# tx_path.net
KiCad netlist of a schematic drawn in Altium Designer
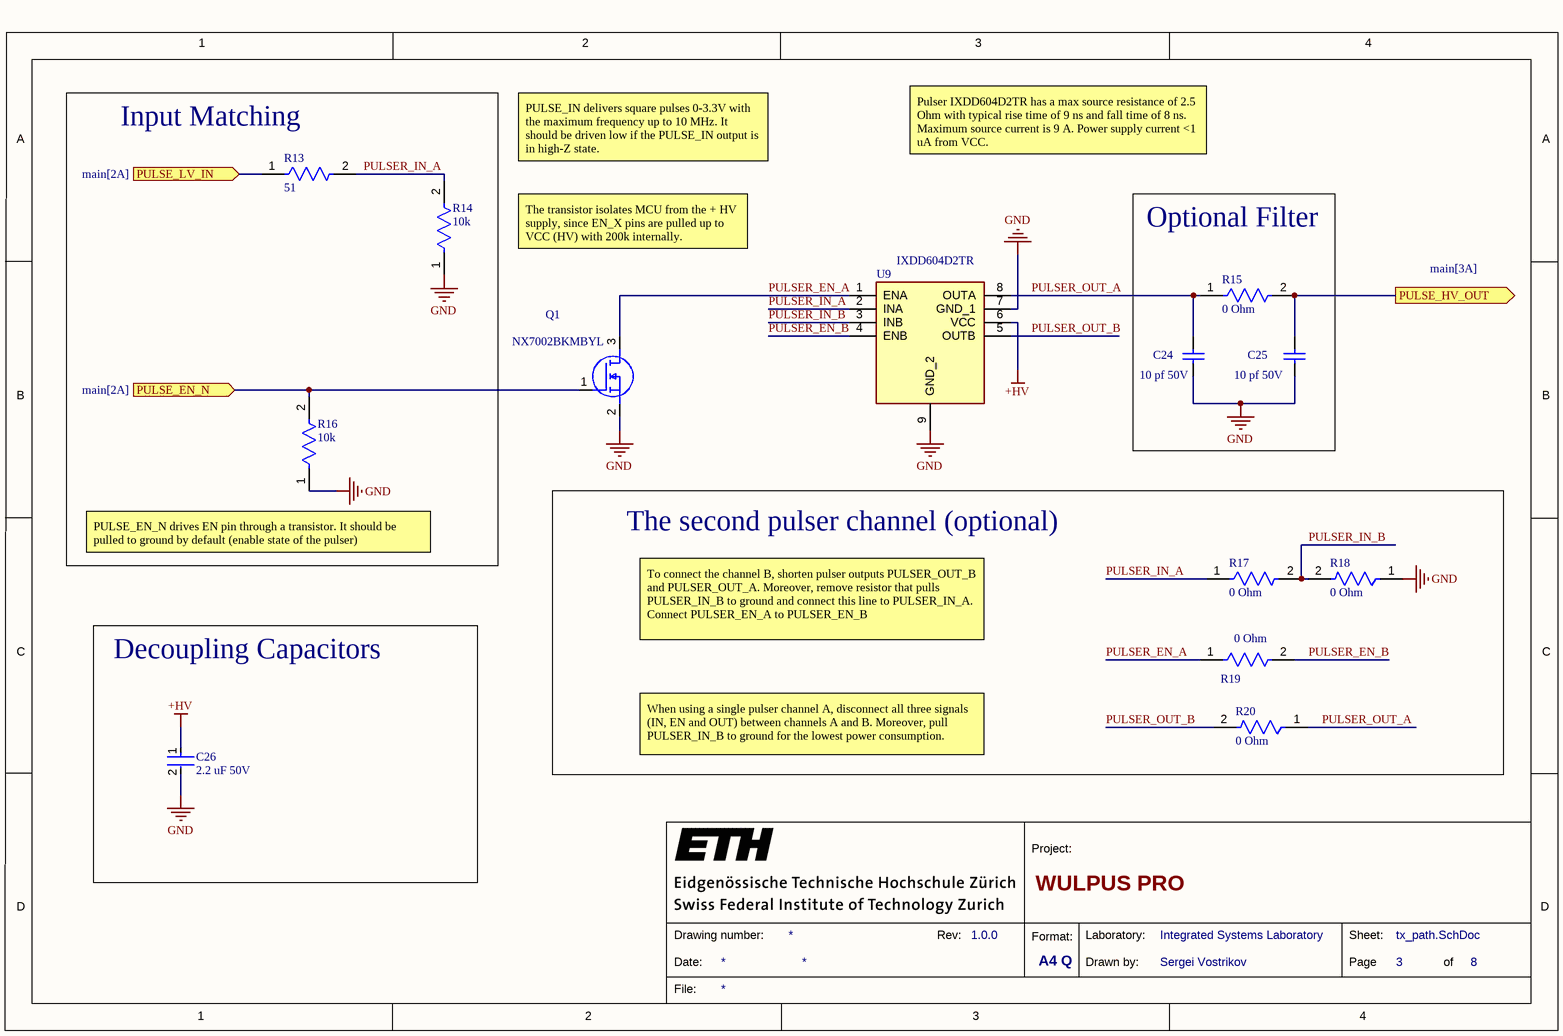
[diagram p0: tx_path.SchDoc]

(export (version "E")
  (design (tool "Eeschema 10.0.6"))
  (components
    (comp (ref "C24")
      (value "10 pf 50V")
      (footprint "CAPC1005X55X25LL05T10")
      (description "GRM1555C1H100JA01D")
      (fields (field (name "MANUFACTURER") "Murata"))
      (libsource (lib "Altium Content Vault") (part "CAP"))
    )
    (comp (ref "C25")
      (value "10 pf 50V")
      (footprint "CAPC1005X55X25LL05T10")
      (description "GRM1555C1H100JA01D")
      (fields (field (name "MANUFACTURER") "Murata"))
      (libsource (lib "Altium Content Vault") (part "CAP"))
    )
    (comp (ref "C26")
      (value "2.2 uF 50V")
      (footprint "FP-GRM188-0_2-IPC_B")
      (description "GRM188R61H225ME11D")
      (fields (field (name "TOLERANCE") "20%"))
      (libsource (lib "Altium Content Vault") (part "11868f565c42a9108669ba33697ecf6"))
    )
    (comp (ref "Q1")
      (value "NX7002BKMBYL")
      (footprint "SamacSys:NX7002BKMBYL")
      (description "MOSFET (N-Channel)")
      (fields (field (name "MOUSER PART NUMBER") "771-NX7002BKMBYL"))
      (libsource (lib "*") (part "NX7002BKMBYL"))
    )
    (comp (ref "R13")
      (value "51")
      (footprint "FP-CRCW0402-e3-IPC_C")
      (description "CRCW040251R0JNED")
      (fields (field (name "TOLERANCE") "5%"))
      (libsource (lib "Altium Content Vault") (part "1029c3af85768c4190bb7ad29bc67b5"))
    )
    (comp (ref "R14")
      (value "10k")
      (footprint "FP-CRCW0402-e3-IPC_B")
      (description "CRCW040210K0JNED")
      (fields (field (name "TOLERANCE") "5%"))
      (libsource (lib "Altium Content Vault") (part "1029c3af85768c4190bb7ad29bc67b5"))
    )
    (comp (ref "R15")
      (value "0 Ohm")
      (footprint "FP-ERJ-3GEY0R00V-MFG")
      (description "ERJ-3GEY0R00V")
      (fields (field (name "TOLERANCE") "5%") (field (name "MANUFACTURER") "Panasonic"))
      (libsource (lib "Altium Content Vault") (part "1029c3af85768c4190bb7ad29bc67b5"))
    )
    (comp (ref "R16")
      (value "10k")
      (footprint "FP-CRCW0402-e3-IPC_B")
      (description "CRCW040210K0JNED")
      (fields (field (name "TOLERANCE") "5%"))
      (libsource (lib "Altium Content Vault") (part "1029c3af85768c4190bb7ad29bc67b5"))
    )
    (comp (ref "R17")
      (value "0 Ohm")
      (footprint "FP-CRCW0402-e3-IPC_C")
      (description "CRCW04020000Z0ED")
      (fields (field (name "TOLERANCE") "5%"))
      (libsource (lib "Altium Content Vault") (part "1029c3af85768c4190bb7ad29bc67b5"))
    )
    (comp (ref "R18")
      (value "0 Ohm")
      (footprint "FP-CRCW0402-e3-IPC_C")
      (description "CRCW04020000Z0ED")
      (fields (field (name "TOLERANCE") "5%"))
      (libsource (lib "Altium Content Vault") (part "1029c3af85768c4190bb7ad29bc67b5"))
    )
    (comp (ref "R19")
      (value "0 Ohm")
      (footprint "FP-CRCW0402-e3-IPC_C")
      (description "CRCW04020000Z0ED")
      (fields (field (name "TOLERANCE") "5%"))
      (libsource (lib "Altium Content Vault") (part "1029c3af85768c4190bb7ad29bc67b5"))
    )
    (comp (ref "R20")
      (value "0 Ohm")
      (footprint "FP-CRCW0402-e3-IPC_C")
      (description "CRCW04020000Z0ED")
      (fields (field (name "TOLERANCE") "5%"))
      (libsource (lib "Altium Content Vault") (part "1029c3af85768c4190bb7ad29bc67b5"))
    )
    (comp (ref "U9")
      (value "IXDD604D2TR")
      (footprint "SamacSys:SON95P500X400X100-9N")
      (description "Integrated Circuit")
      (fields (field (name "MOUSER PART NUMBER") "849-IXDD604D2TR"))
      (libsource (lib "SamacSys") (part "IXDD604D2TR"))
    )
  )
  (nets
    (net (code "1") (name "+HV") (class "Default")
      (node (ref "C26") (pin "1") (pinfunction "1_1") (pintype "passive"))
      (node (ref "U9") (pin "6") (pinfunction "VCC_6") (pintype "passive"))
    )
    (net (code "3") (name "/PULSER_EN_A") (class "Default")
      (node (ref "Q1") (pin "3") (pinfunction "D_3") (pintype "passive"))
      (node (ref "R19") (pin "1") (pinfunction "1_1") (pintype "passive"))
      (node (ref "U9") (pin "1") (pinfunction "ENA_1") (pintype "passive"))
    )
    (net (code "4") (name "/PULSER_EN_B") (class "Default")
      (node (ref "R19") (pin "2") (pinfunction "2_2") (pintype "passive"))
      (node (ref "U9") (pin "4") (pinfunction "ENB_4") (pintype "passive"))
    )
    (net (code "5") (name "/PULSER_IN_A") (class "Default")
      (node (ref "R13") (pin "2") (pinfunction "2_2") (pintype "passive"))
      (node (ref "R14") (pin "2") (pinfunction "2_2") (pintype "passive"))
      (node (ref "R17") (pin "1") (pinfunction "1_1") (pintype "passive"))
      (node (ref "U9") (pin "2") (pinfunction "INA_2") (pintype "passive"))
    )
    (net (code "6") (name "/PULSER_IN_B") (class "Default")
      (node (ref "R17") (pin "2") (pinfunction "2_2") (pintype "passive"))
      (node (ref "R18") (pin "2") (pinfunction "2_2") (pintype "passive"))
      (node (ref "U9") (pin "3") (pinfunction "INB_3") (pintype "passive"))
    )
    (net (code "7") (name "/PULSER_OUT_A") (class "Default")
      (node (ref "C24") (pin "2") (pinfunction "2_2") (pintype "passive"))
      (node (ref "R15") (pin "1") (pinfunction "1_1") (pintype "passive"))
      (node (ref "R20") (pin "1") (pinfunction "1_1") (pintype "passive"))
      (node (ref "U9") (pin "8") (pinfunction "OUTA_8") (pintype "passive"))
    )
    (net (code "8") (name "/PULSER_OUT_B") (class "Default")
      (node (ref "R20") (pin "2") (pinfunction "2_2") (pintype "passive"))
      (node (ref "U9") (pin "5") (pinfunction "OUTB_5") (pintype "passive"))
    )
    (net (code "9") (name "/PULSE_EN_N") (class "Default")
      (node (ref "Q1") (pin "1") (pinfunction "G_1") (pintype "passive"))
      (node (ref "R16") (pin "2") (pinfunction "2_2") (pintype "passive"))
    )
    (net (code "10") (name "/PULSE_HV_OUT") (class "Default")
      (node (ref "C25") (pin "2") (pinfunction "2_2") (pintype "passive"))
      (node (ref "R15") (pin "2") (pinfunction "2_2") (pintype "passive"))
    )
    (net (code "11") (name "/PULSE_LV_IN") (class "Default")
      (node (ref "R13") (pin "1") (pinfunction "1_1") (pintype "passive"))
    )
    (net (code "12") (name "GND") (class "Default")
      (node (ref "C24") (pin "1") (pinfunction "1_1") (pintype "passive"))
      (node (ref "C25") (pin "1") (pinfunction "1_1") (pintype "passive"))
      (node (ref "C26") (pin "2") (pinfunction "2_2") (pintype "passive"))
      (node (ref "Q1") (pin "2") (pinfunction "S_2") (pintype "passive"))
      (node (ref "R14") (pin "1") (pinfunction "1_1") (pintype "passive"))
      (node (ref "R16") (pin "1") (pinfunction "1_1") (pintype "passive"))
      (node (ref "R18") (pin "1") (pinfunction "1_1") (pintype "passive"))
      (node (ref "U9") (pin "7") (pinfunction "GND_1_7") (pintype "passive"))
      (node (ref "U9") (pin "9") (pinfunction "GND_2_9") (pintype "passive"))
    )
  )
)
